# 19V-PC-POWER.net
KiCad netlist of a schematic drawn in Altium Designer
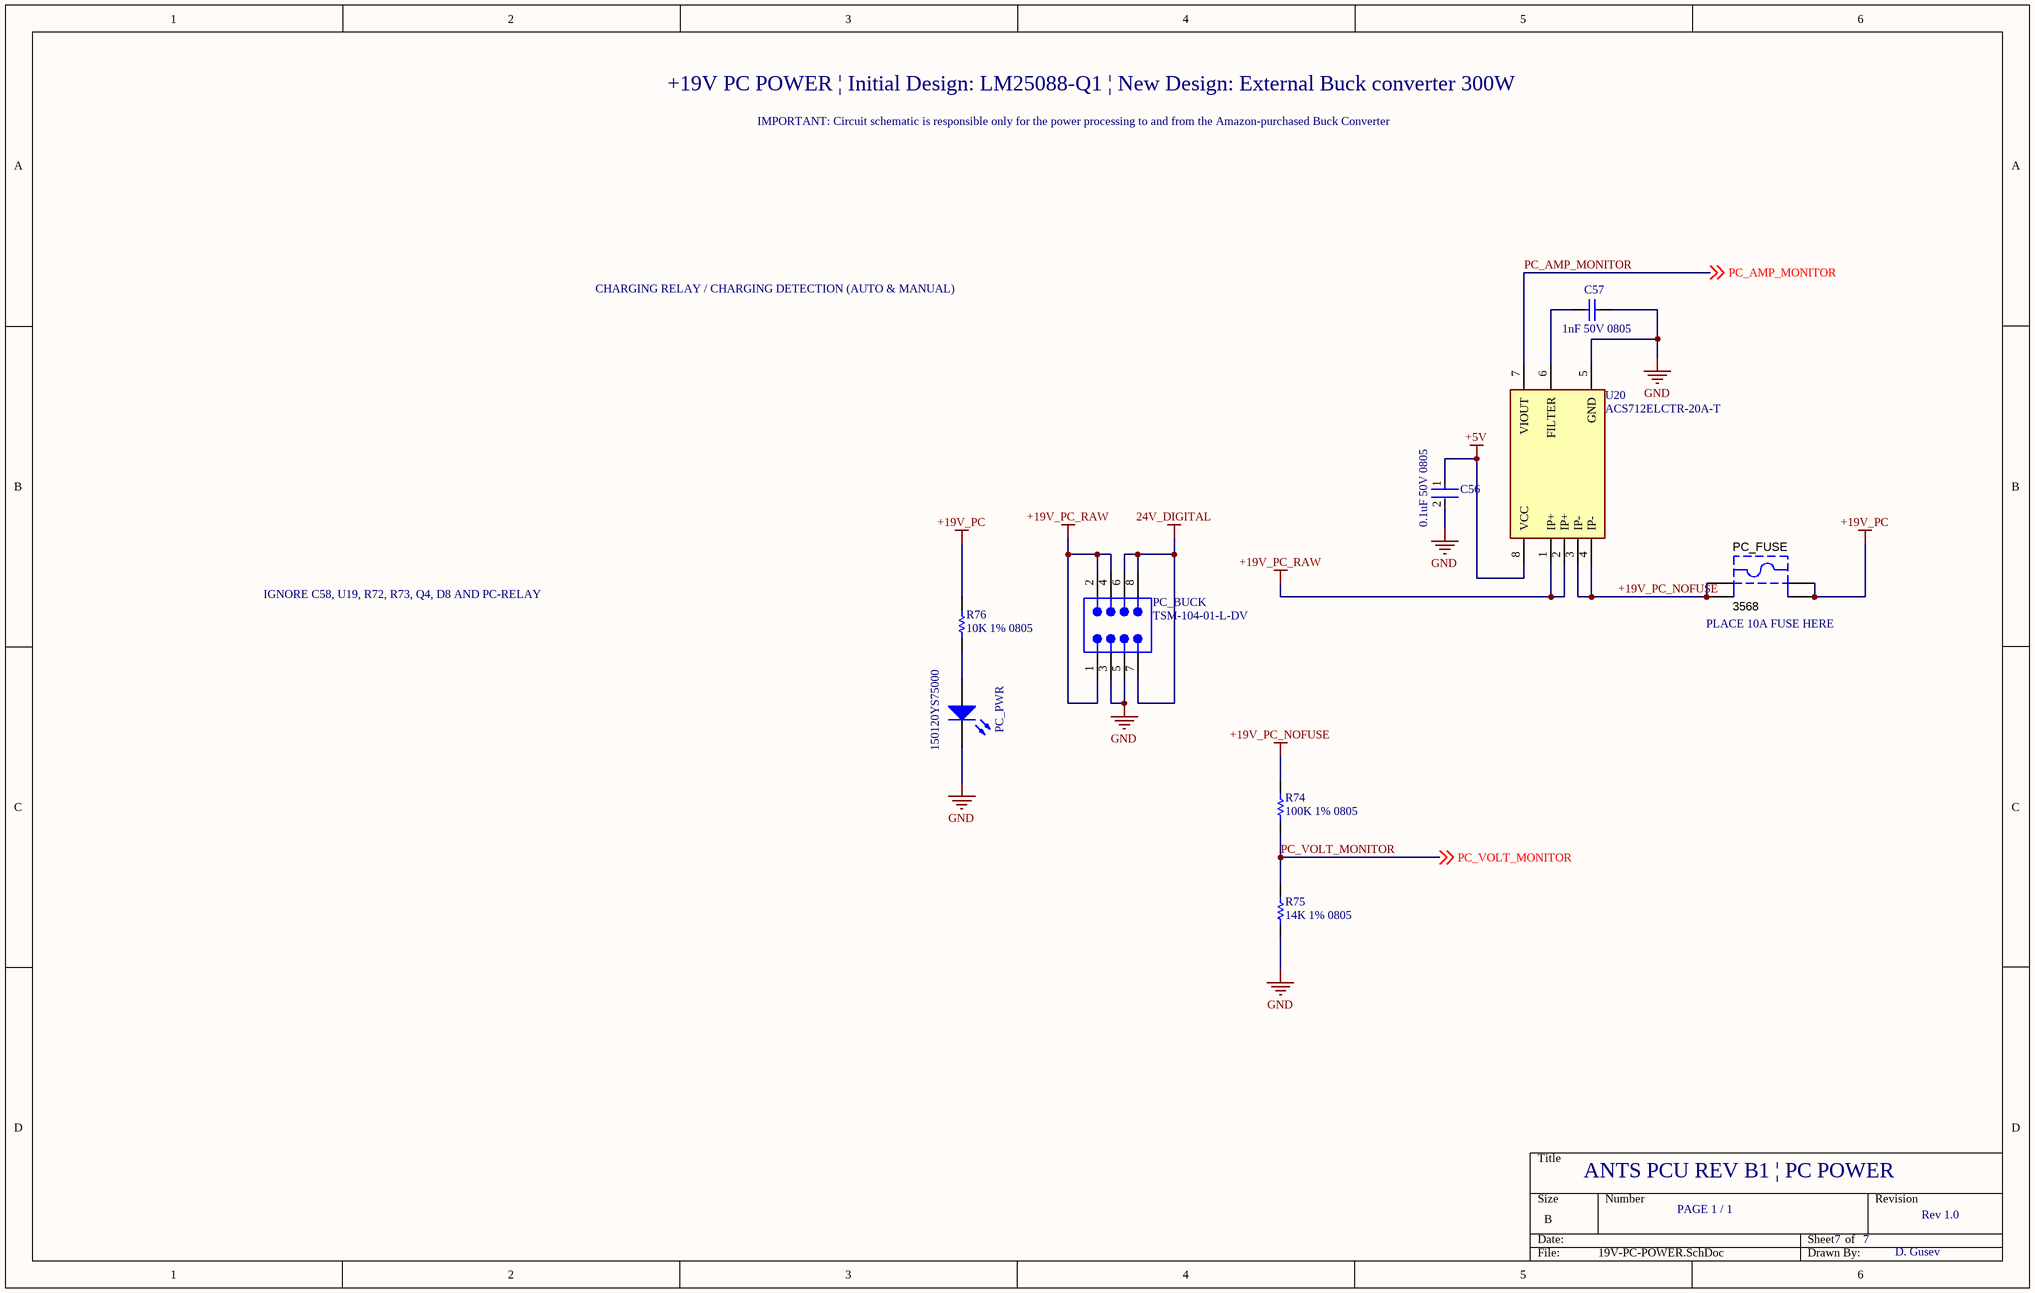
[diagram p0: 19V-PC-POWER.SchDoc]

(export (version "E")
  (design (tool "Eeschema 10.0.6"))
  (components
    (comp (ref "C56")
      (value "0.1uF 50V 0805")
      (footprint "FP-C0805C-DN-MFG")
      (description "CAP CER 0.1UF 50V X7R 0805")
      (fields
        (field (name "MANUFACTURER PART NUMBER") "C0805C104K5RACTU")
        (field (name "MANUFACTURER") "KEMET")
      )
      (libsource (lib "Altium Content Vault") (part "b4654b650e69147ec39a6b967a45e02"))
    )
    (comp (ref "C57")
      (value "1nF 50V 0805")
      (footprint "CAPC2013X94X50ML20T25")
      (fields
        (field (name "PART NUMBER") "08055C102KAT2A.")
        (field (name "MANUFACTURER") "AVX Interconnect / Elco")
      )
      (libsource (lib "Altium Content Vault") (part "CAP"))
    )
    (comp (ref "PC_BUCK")
      (value "TSM-104-01-L-DV")
      (footprint "SMTC-TSM-104-01-X-DV")
      (description "0.025\" SQ Post Header, Surface Mount, Vertical, -55 to 125 degC, 2.54 mm Pitch, 8-Pin, Male, RoHS")
      (fields (field (name "MANUFACTURER") "Samtec"))
      (libsource (lib "Altium Content Vault") (part "SMTC-TSM-104-01-X-X"))
    )
    (comp (ref "PC_FUSE")
      (value "3568")
      (footprint "KSTN-3568_V")
      (description "Fuse Holder, 20 A, 500 V, -50 to 145 degC, 4-Pin THD, RoHS")
      (fields (field (name "MANUFACTURER") "Keystone"))
      (libsource (lib "Altium Content Vault") (part "FUSE_HOLDER-4"))
    )
    (comp (ref "PC_PWR")
      (value "150120YS75000")
      (footprint "1206_A")
      (description "SMD mono-color Chip LED, WL-SMCW, Yellow")
      (fields (field (name "MANUFACTURER") "Wuerth Elektronik"))
      (libsource (lib "Altium Content Vault") (part "WE-LED_K1A2-2"))
    )
    (comp (ref "R74")
      (value "100K 1% 0805")
      (footprint "RESC2013X60X35ML10T20")
      (description "Chip Resistor, 100 KOhm, +/- 1%, 0.125 W, -55 to 155 degC, 0805 (2012 Metric), RoHS, Tape and Reel")
      (fields (field (name "MANUFACTURER") "Yageo") (field (name "TOLERANCE") "1%"))
      (libsource (lib "Altium Content Vault") (part "RES-2"))
    )
    (comp (ref "R75")
      (value "14K 1% 0805")
      (footprint "RESC2013X60X35LL10T20")
      (fields (field (name "PART NUMBER") "RC0805FR-0714KL") (field (name "MANUFACTURER") "Yageo"))
      (libsource (lib "Altium Content Vault") (part "RES"))
    )
    (comp (ref "R76")
      (value "10K 1% 0805")
      (footprint "RESC2013X60X35NL10T20")
      (description "Chip Resistor, 10 KOhm, +/- 1%, 0.125 W, -55 to 155 degC, 0805 (2012 Metric), RoHS, Tape and Reel")
      (fields (field (name "MANUFACTURER") "Yageo"))
      (libsource (lib "Altium Content Vault") (part "RES-2"))
    )
    (comp (ref "U20")
      (value "ACS712ELCTR-20A-T")
      (footprint "FP-LC-8-IPC_C")
      (description "SENSOR CURRENT HALL 20A AC/DC")
      (libsource (lib "Altium Content Vault") (part "c67a3b215a6bf96dc401a72103bae39"))
    )
  )
  (nets
    (net (code "1") (name "+5V") (class "Default")
      (node (ref "C56") (pin "1") (pinfunction "1_1") (pintype "passive"))
      (node (ref "U20") (pin "8") (pinfunction "VCC_8") (pintype "power_in"))
    )
    (net (code "2") (name "+19V_PC") (class "Default")
      (node (ref "PC_FUSE") (pin "1") (pinfunction "1_1") (pintype "passive"))
      (node (ref "PC_FUSE") (pin "2") (pinfunction "2_2") (pintype "passive"))
      (node (ref "R76") (pin "1") (pinfunction "1_1") (pintype "passive"))
    )
    (net (code "3") (name "+19V_PC_NOFUSE") (class "Default")
      (node (ref "PC_FUSE") (pin "3") (pinfunction "3_3") (pintype "passive"))
      (node (ref "PC_FUSE") (pin "4") (pinfunction "4_4") (pintype "passive"))
      (node (ref "R74") (pin "2") (pinfunction "2_2") (pintype "passive"))
      (node (ref "U20") (pin "3") (pinfunction "IP-_3") (pintype "passive"))
      (node (ref "U20") (pin "4") (pinfunction "IP-_4") (pintype "passive"))
    )
    (net (code "4") (name "+19V_PC_RAW") (class "Default")
      (node (ref "PC_BUCK") (pin "1") (pinfunction "1_1") (pintype "passive"))
      (node (ref "PC_BUCK") (pin "2") (pinfunction "2_2") (pintype "passive"))
      (node (ref "PC_BUCK") (pin "4") (pinfunction "4_4") (pintype "passive"))
      (node (ref "U20") (pin "1") (pinfunction "IP+_1") (pintype "passive"))
      (node (ref "U20") (pin "2") (pinfunction "IP+_2") (pintype "passive"))
    )
    (net (code "5") (name "24V_DIGITAL") (class "Default")
      (node (ref "PC_BUCK") (pin "6") (pinfunction "6_6") (pintype "passive"))
      (node (ref "PC_BUCK") (pin "7") (pinfunction "7_7") (pintype "passive"))
      (node (ref "PC_BUCK") (pin "8") (pinfunction "8_8") (pintype "passive"))
    )
    (net (code "6") (name "GND") (class "Default")
      (node (ref "C56") (pin "2") (pinfunction "2_2") (pintype "passive"))
      (node (ref "C57") (pin "2") (pinfunction "2_2") (pintype "passive"))
      (node (ref "PC_BUCK") (pin "3") (pinfunction "3_3") (pintype "passive"))
      (node (ref "PC_BUCK") (pin "5") (pinfunction "5_5") (pintype "passive"))
      (node (ref "PC_PWR") (pin "1") (pinfunction "K_1") (pintype "passive"))
      (node (ref "R75") (pin "1") (pinfunction "1_1") (pintype "passive"))
      (node (ref "U20") (pin "5") (pinfunction "GND_5") (pintype "power_in"))
    )
    (net (code "7") (name "Net-(PC_PWR-A)") (class "Default")
      (node (ref "PC_PWR") (pin "2") (pinfunction "A_2") (pintype "passive"))
      (node (ref "R76") (pin "2") (pinfunction "2_2") (pintype "passive"))
    )
    (net (code "8") (name "Net-(U20-FILTER)") (class "Default")
      (node (ref "C57") (pin "1") (pinfunction "1_1") (pintype "passive"))
      (node (ref "U20") (pin "6") (pinfunction "FILTER_6") (pintype "passive"))
    )
    (net (code "9") (name "PC_AMP_MONITOR") (class "Default")
      (node (ref "U20") (pin "7") (pinfunction "VIOUT_7") (pintype "passive"))
    )
    (net (code "10") (name "PC_VOLT_MONITOR") (class "Default")
      (node (ref "R74") (pin "1") (pinfunction "1_1") (pintype "passive"))
      (node (ref "R75") (pin "2") (pinfunction "2_2") (pintype "passive"))
    )
  )
)
